# ProgrammateurFilPilote_1_1.net
KiCad netlist of a schematic drawn in EAGLE
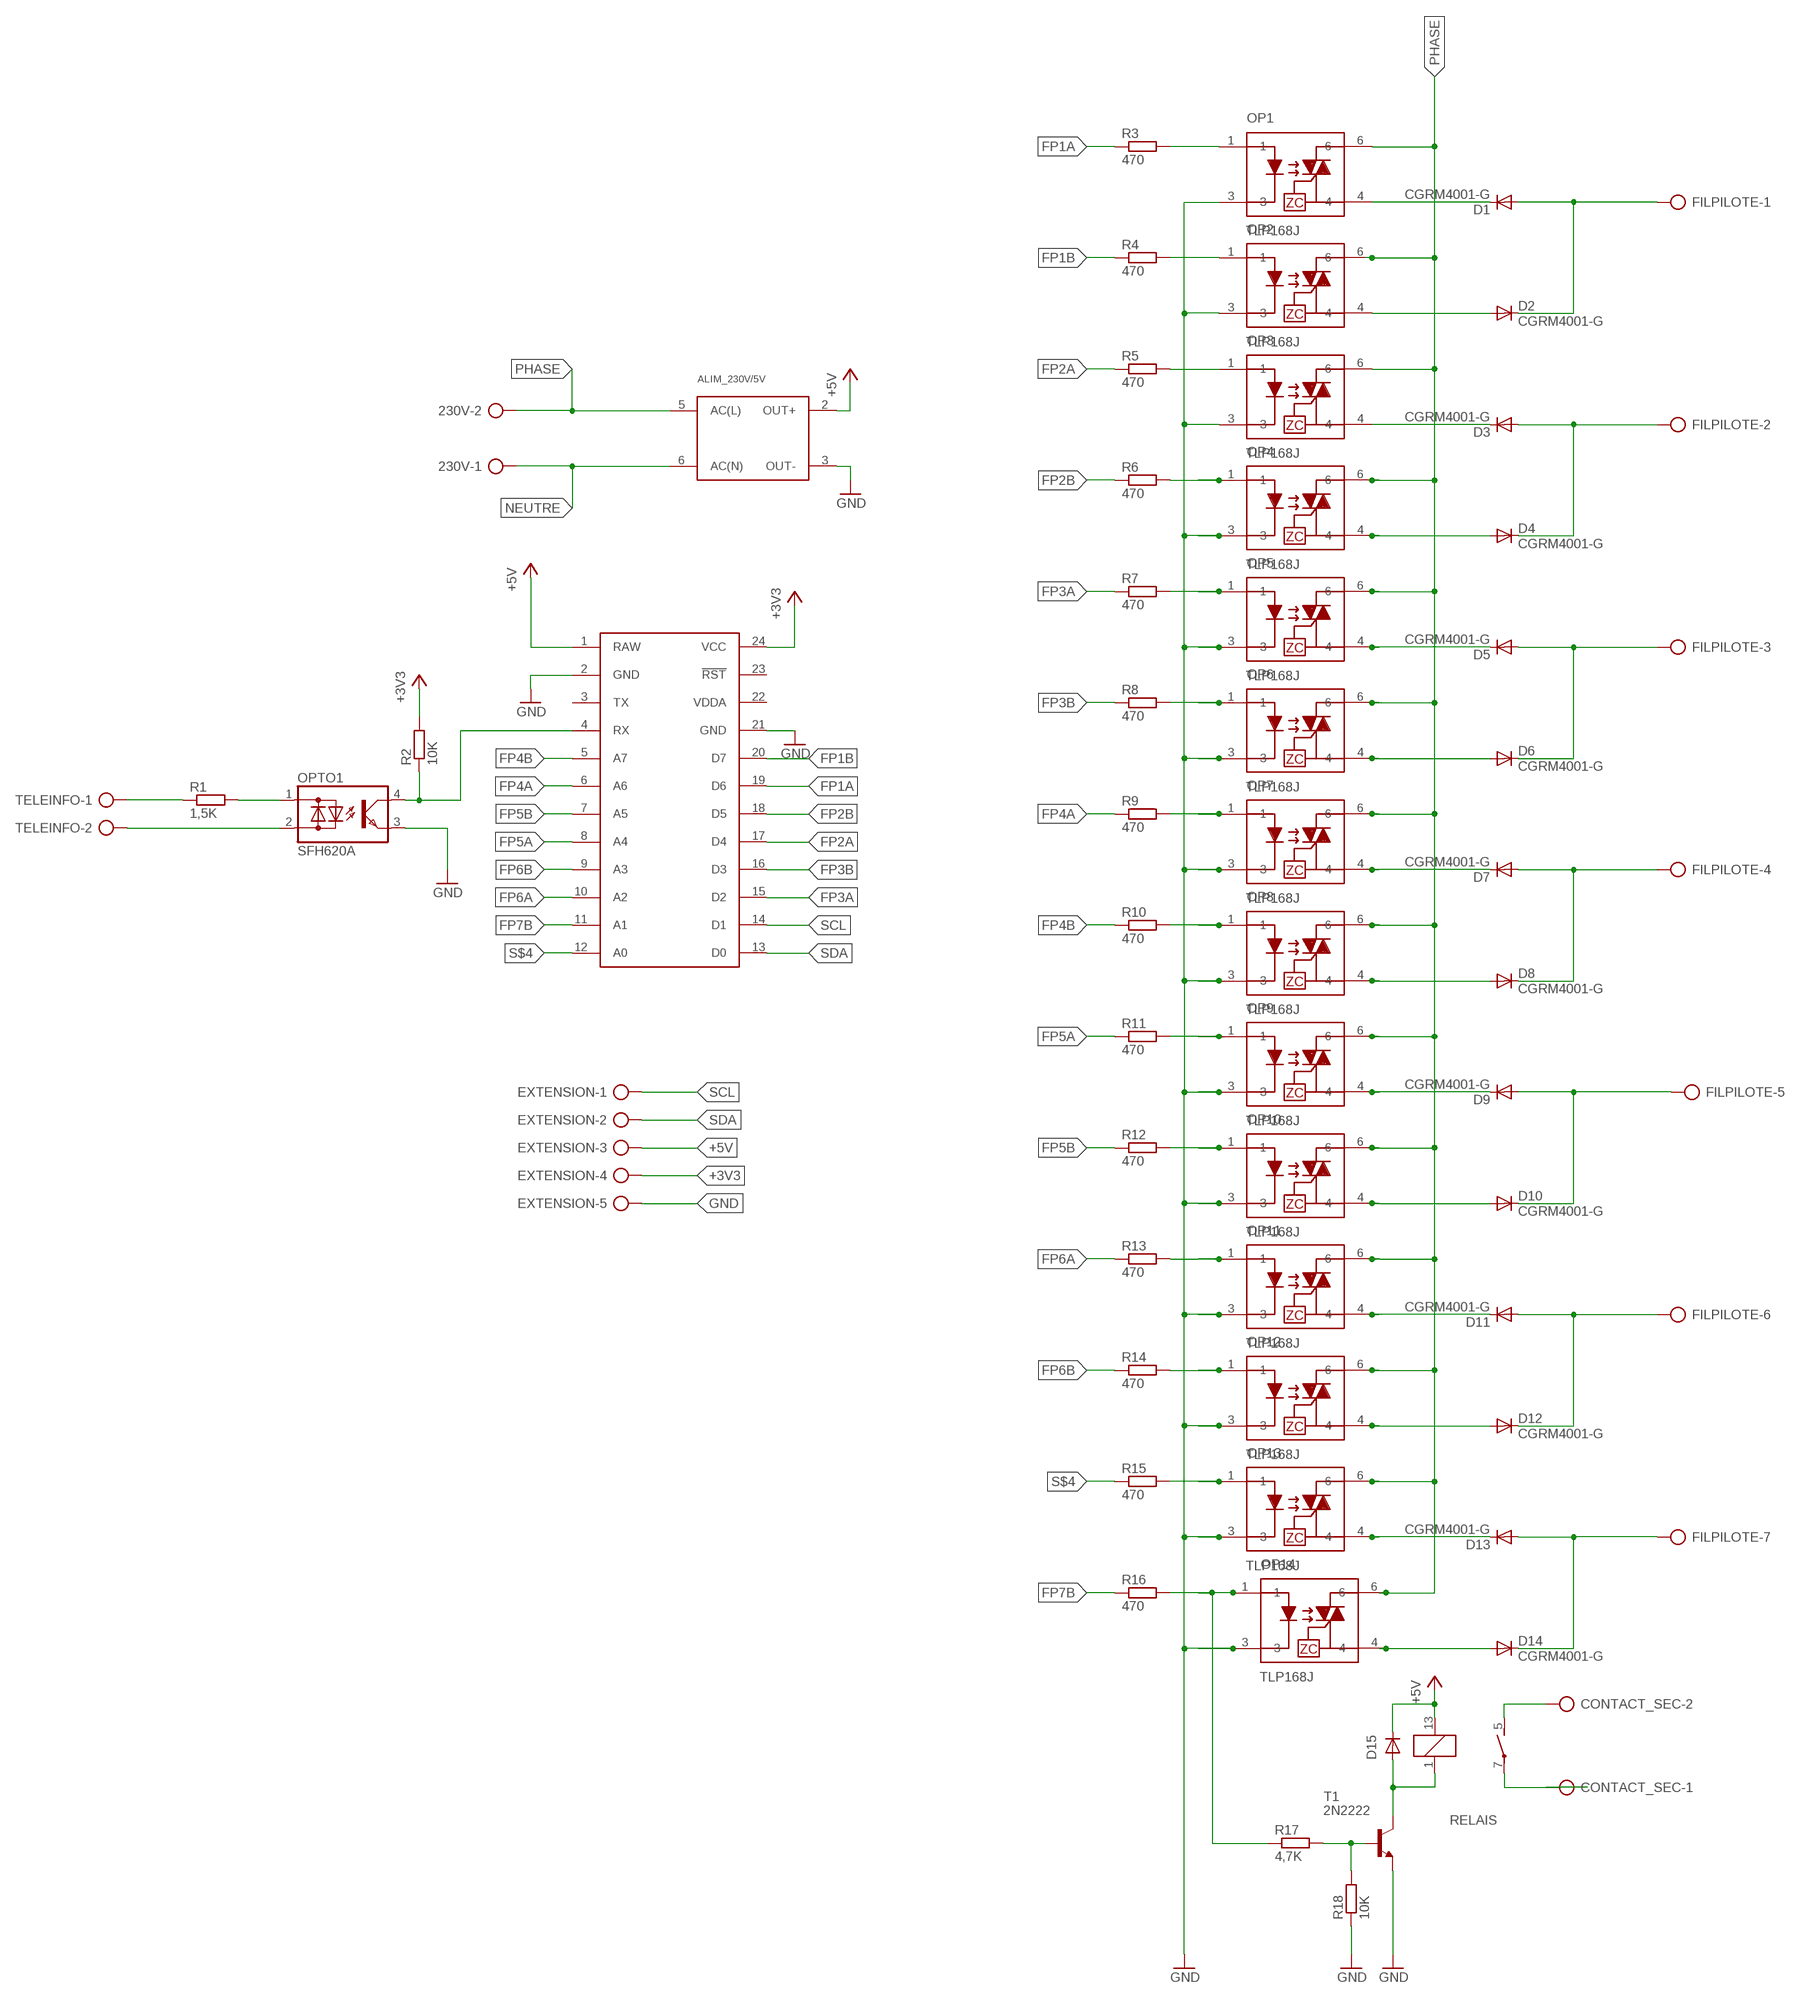
[diagram p0: schematic, sheet 1]

(export (version "E")
  (design (tool "Eeschema 10.0.6"))
  (components
    (comp (ref "230V")
      (value "AK500/2")
      (footprint "eagle-import:AK500_2")
      (libsource (lib "eagle-import") (part "AK500/2"))
    )
    (comp (ref "ALIM_230V/5V")
      (value "TMLM04-SINGLE")
      (footprint "eagle-import:TMLM04")
      (libsource (lib "eagle-import") (part "TMLM04-SINGLE"))
    )
    (comp (ref "CONTACT_SEC")
      (value "AK500/2")
      (footprint "eagle-import:AK500_2")
      (libsource (lib "eagle-import") (part "AK500/2"))
    )
    (comp (ref "D1")
      (value "CGRM4001-G")
      (footprint "eagle-import:SOD-123_MINI-SMA")
      (libsource (lib "eagle-import") (part "CGRM400-G1"))
    )
    (comp (ref "D2")
      (value "CGRM4001-G")
      (footprint "eagle-import:SOD-123_MINI-SMA")
      (libsource (lib "eagle-import") (part "CGRM400-G1"))
    )
    (comp (ref "D3")
      (value "CGRM4001-G")
      (footprint "eagle-import:SOD-123_MINI-SMA")
      (libsource (lib "eagle-import") (part "CGRM400-G1"))
    )
    (comp (ref "D4")
      (value "CGRM4001-G")
      (footprint "eagle-import:SOD-123_MINI-SMA")
      (libsource (lib "eagle-import") (part "CGRM400-G1"))
    )
    (comp (ref "D5")
      (value "CGRM4001-G")
      (footprint "eagle-import:SOD-123_MINI-SMA")
      (libsource (lib "eagle-import") (part "CGRM400-G1"))
    )
    (comp (ref "D6")
      (value "CGRM4001-G")
      (footprint "eagle-import:SOD-123_MINI-SMA")
      (libsource (lib "eagle-import") (part "CGRM400-G1"))
    )
    (comp (ref "D7")
      (value "CGRM4001-G")
      (footprint "eagle-import:SOD-123_MINI-SMA")
      (libsource (lib "eagle-import") (part "CGRM400-G1"))
    )
    (comp (ref "D8")
      (value "CGRM4001-G")
      (footprint "eagle-import:SOD-123_MINI-SMA")
      (libsource (lib "eagle-import") (part "CGRM400-G1"))
    )
    (comp (ref "D9")
      (value "CGRM4001-G")
      (footprint "eagle-import:SOD-123_MINI-SMA")
      (libsource (lib "eagle-import") (part "CGRM400-G1"))
    )
    (comp (ref "D10")
      (value "CGRM4001-G")
      (footprint "eagle-import:SOD-123_MINI-SMA")
      (libsource (lib "eagle-import") (part "CGRM400-G1"))
    )
    (comp (ref "D11")
      (value "CGRM4001-G")
      (footprint "eagle-import:SOD-123_MINI-SMA")
      (libsource (lib "eagle-import") (part "CGRM400-G1"))
    )
    (comp (ref "D12")
      (value "CGRM4001-G")
      (footprint "eagle-import:SOD-123_MINI-SMA")
      (libsource (lib "eagle-import") (part "CGRM400-G1"))
    )
    (comp (ref "D13")
      (value "CGRM4001-G")
      (footprint "eagle-import:SOD-123_MINI-SMA")
      (libsource (lib "eagle-import") (part "CGRM400-G1"))
    )
    (comp (ref "D14")
      (value "CGRM4001-G")
      (footprint "eagle-import:SOD-123_MINI-SMA")
      (libsource (lib "eagle-import") (part "CGRM400-G1"))
    )
    (comp (ref "D15")
      (value "CGRM4001-G")
      (footprint "eagle-import:SOD-123_MINI-SMA")
      (libsource (lib "eagle-import") (part "CGRM400-G1"))
    )
    (comp (ref "EXTENSION")
      (value "AK500/5")
      (footprint "eagle-import:AK500_5")
      (libsource (lib "eagle-import") (part "AK500/5"))
    )
    (comp (ref "FILPILOTE")
      (value "AK500/7")
      (footprint "eagle-import:AK500_7")
      (libsource (lib "eagle-import") (part "AK500/7"))
    )
    (comp (ref "OP1")
      (value "TLP168J")
      (footprint "eagle-import:MFSOP-4")
      (libsource (lib "eagle-import") (part "TLP168J"))
    )
    (comp (ref "OP2")
      (value "TLP168J")
      (footprint "eagle-import:MFSOP-4")
      (libsource (lib "eagle-import") (part "TLP168J"))
    )
    (comp (ref "OP3")
      (value "TLP168J")
      (footprint "eagle-import:MFSOP-4")
      (libsource (lib "eagle-import") (part "TLP168J"))
    )
    (comp (ref "OP4")
      (value "TLP168J")
      (footprint "eagle-import:MFSOP-4")
      (libsource (lib "eagle-import") (part "TLP168J"))
    )
    (comp (ref "OP5")
      (value "TLP168J")
      (footprint "eagle-import:MFSOP-4")
      (libsource (lib "eagle-import") (part "TLP168J"))
    )
    (comp (ref "OP6")
      (value "TLP168J")
      (footprint "eagle-import:MFSOP-4")
      (libsource (lib "eagle-import") (part "TLP168J"))
    )
    (comp (ref "OP7")
      (value "TLP168J")
      (footprint "eagle-import:MFSOP-4")
      (libsource (lib "eagle-import") (part "TLP168J"))
    )
    (comp (ref "OP8")
      (value "TLP168J")
      (footprint "eagle-import:MFSOP-4")
      (libsource (lib "eagle-import") (part "TLP168J"))
    )
    (comp (ref "OP9")
      (value "TLP168J")
      (footprint "eagle-import:MFSOP-4")
      (libsource (lib "eagle-import") (part "TLP168J"))
    )
    (comp (ref "OP10")
      (value "TLP168J")
      (footprint "eagle-import:MFSOP-4")
      (libsource (lib "eagle-import") (part "TLP168J"))
    )
    (comp (ref "OP11")
      (value "TLP168J")
      (footprint "eagle-import:MFSOP-4")
      (libsource (lib "eagle-import") (part "TLP168J"))
    )
    (comp (ref "OP12")
      (value "TLP168J")
      (footprint "eagle-import:MFSOP-4")
      (libsource (lib "eagle-import") (part "TLP168J"))
    )
    (comp (ref "OP13")
      (value "TLP168J")
      (footprint "eagle-import:MFSOP-4")
      (libsource (lib "eagle-import") (part "TLP168J"))
    )
    (comp (ref "OP14")
      (value "TLP168J")
      (footprint "eagle-import:MFSOP-4")
      (libsource (lib "eagle-import") (part "TLP168J"))
    )
    (comp (ref "OPTO1")
      (value "SFH620A")
      (footprint "eagle-import:DIL04")
      (fields (field (name "MPN") "SFH620A-2"))
      (libsource (lib "eagle-import") (part "SFH620A"))
    )
    (comp (ref "R1")
      (value "1,5K")
      (footprint "eagle-import:R1206")
      (libsource (lib "eagle-import") (part "R-EU_R1206"))
    )
    (comp (ref "R2")
      (value "10K")
      (footprint "eagle-import:R1206")
      (libsource (lib "eagle-import") (part "R-EU_R1206"))
    )
    (comp (ref "R3")
      (value "470")
      (footprint "eagle-import:R1206")
      (libsource (lib "eagle-import") (part "R-EU_R1206"))
    )
    (comp (ref "R4")
      (value "470")
      (footprint "eagle-import:R1206")
      (libsource (lib "eagle-import") (part "R-EU_R1206"))
    )
    (comp (ref "R5")
      (value "470")
      (footprint "eagle-import:R1206")
      (libsource (lib "eagle-import") (part "R-EU_R1206"))
    )
    (comp (ref "R6")
      (value "470")
      (footprint "eagle-import:R1206")
      (libsource (lib "eagle-import") (part "R-EU_R1206"))
    )
    (comp (ref "R7")
      (value "470")
      (footprint "eagle-import:R1206")
      (libsource (lib "eagle-import") (part "R-EU_R1206"))
    )
    (comp (ref "R8")
      (value "470")
      (footprint "eagle-import:R1206")
      (libsource (lib "eagle-import") (part "R-EU_R1206"))
    )
    (comp (ref "R9")
      (value "470")
      (footprint "eagle-import:R1206")
      (libsource (lib "eagle-import") (part "R-EU_R1206"))
    )
    (comp (ref "R10")
      (value "470")
      (footprint "eagle-import:R1206")
      (libsource (lib "eagle-import") (part "R-EU_R1206"))
    )
    (comp (ref "R11")
      (value "470")
      (footprint "eagle-import:R1206")
      (libsource (lib "eagle-import") (part "R-EU_R1206"))
    )
    (comp (ref "R12")
      (value "470")
      (footprint "eagle-import:R1206")
      (libsource (lib "eagle-import") (part "R-EU_R1206"))
    )
    (comp (ref "R13")
      (value "470")
      (footprint "eagle-import:R1206")
      (libsource (lib "eagle-import") (part "R-EU_R1206"))
    )
    (comp (ref "R14")
      (value "470")
      (footprint "eagle-import:R1206")
      (libsource (lib "eagle-import") (part "R-EU_R1206"))
    )
    (comp (ref "R15")
      (value "470")
      (footprint "eagle-import:R1206")
      (libsource (lib "eagle-import") (part "R-EU_R1206"))
    )
    (comp (ref "R16")
      (value "470")
      (footprint "eagle-import:R1206")
      (libsource (lib "eagle-import") (part "R-EU_R1206"))
    )
    (comp (ref "R17")
      (value "4,7K")
      (footprint "eagle-import:R1206")
      (libsource (lib "eagle-import") (part "R-EU_R1206"))
    )
    (comp (ref "R18")
      (value "10K")
      (footprint "eagle-import:R1206")
      (libsource (lib "eagle-import") (part "R-EU_R1206"))
    )
    (comp (ref "RELAIS")
      (value "Relais G6D")
      (footprint "eagle-import:G6D")
      (libsource (lib "eagle-import") (part "G6D?-1A-ASI12VDC"))
    )
    (comp (ref "SPARKCORE")
      (value "SPARK_CORECORE")
      (footprint "eagle-import:SPARK_CORE")
      (libsource (lib "eagle-import") (part "SPARK_CORECORE"))
    )
    (comp (ref "T1")
      (value "2N2222")
      (footprint "eagle-import:TO92-EBC")
      (libsource (lib "eagle-import") (part "-NPN-TO92-EBC2N2222"))
    )
    (comp (ref "TELEINFO")
      (value "AK500/2")
      (footprint "eagle-import:AK500_2")
      (libsource (lib "eagle-import") (part "AK500/2"))
    )
  )
  (nets
    (net (code "1") (name "+3V3") (class "Default")
      (node (ref "EXTENSION") (pin "4") (pinfunction "KL_4") (pintype "passive"))
      (node (ref "R2") (pin "2") (pinfunction "2_2") (pintype "passive"))
      (node (ref "SPARKCORE") (pin "24") (pinfunction "VCC_24") (pintype "power_in"))
    )
    (net (code "2") (name "+5V") (class "Default")
      (node (ref "ALIM_230V/5V") (pin "2") (pinfunction "OUT+_2") (pintype "passive"))
      (node (ref "D15") (pin "C") (pinfunction "C_C") (pintype "passive"))
      (node (ref "EXTENSION") (pin "3") (pinfunction "KL_3") (pintype "passive"))
      (node (ref "RELAIS") (pin "13") (pinfunction "2_13") (pintype "passive"))
      (node (ref "SPARKCORE") (pin "1") (pinfunction "RAW_1") (pintype "power_in"))
    )
    (net (code "3") (name "/VDDA") (class "Default")
      (node (ref "SPARKCORE") (pin "22") (pinfunction "VDDA_22") (pintype "power_in"))
    )
    (net (code "4") (name "FP1A") (class "Default")
      (node (ref "R3") (pin "1") (pinfunction "1_1") (pintype "passive"))
      (node (ref "SPARKCORE") (pin "19") (pinfunction "D6_19") (pintype "bidirectional"))
    )
    (net (code "5") (name "FP1B") (class "Default")
      (node (ref "R4") (pin "1") (pinfunction "1_1") (pintype "passive"))
      (node (ref "SPARKCORE") (pin "20") (pinfunction "D7_20") (pintype "bidirectional"))
    )
    (net (code "6") (name "FP2A") (class "Default")
      (node (ref "R5") (pin "1") (pinfunction "1_1") (pintype "passive"))
      (node (ref "SPARKCORE") (pin "17") (pinfunction "D4_17") (pintype "bidirectional"))
    )
    (net (code "7") (name "FP2B") (class "Default")
      (node (ref "R6") (pin "1") (pinfunction "1_1") (pintype "passive"))
      (node (ref "SPARKCORE") (pin "18") (pinfunction "D5_18") (pintype "bidirectional"))
    )
    (net (code "8") (name "FP3A") (class "Default")
      (node (ref "R7") (pin "1") (pinfunction "1_1") (pintype "passive"))
      (node (ref "SPARKCORE") (pin "15") (pinfunction "D2_15") (pintype "bidirectional"))
    )
    (net (code "9") (name "FP3B") (class "Default")
      (node (ref "R8") (pin "1") (pinfunction "1_1") (pintype "passive"))
      (node (ref "SPARKCORE") (pin "16") (pinfunction "D3_16") (pintype "bidirectional"))
    )
    (net (code "10") (name "FP4A") (class "Default")
      (node (ref "R9") (pin "1") (pinfunction "1_1") (pintype "passive"))
      (node (ref "SPARKCORE") (pin "6") (pinfunction "A6_6") (pintype "bidirectional"))
    )
    (net (code "11") (name "FP4B") (class "Default")
      (node (ref "R10") (pin "1") (pinfunction "1_1") (pintype "passive"))
      (node (ref "SPARKCORE") (pin "5") (pinfunction "A7_5") (pintype "bidirectional"))
    )
    (net (code "12") (name "FP5A") (class "Default")
      (node (ref "R11") (pin "1") (pinfunction "1_1") (pintype "passive"))
      (node (ref "SPARKCORE") (pin "8") (pinfunction "A4_8") (pintype "bidirectional"))
    )
    (net (code "13") (name "FP5B") (class "Default")
      (node (ref "R12") (pin "1") (pinfunction "1_1") (pintype "passive"))
      (node (ref "SPARKCORE") (pin "7") (pinfunction "A5_7") (pintype "bidirectional"))
    )
    (net (code "14") (name "FP6A") (class "Default")
      (node (ref "R13") (pin "1") (pinfunction "1_1") (pintype "passive"))
      (node (ref "SPARKCORE") (pin "10") (pinfunction "A2_10") (pintype "bidirectional"))
    )
    (net (code "15") (name "FP6B") (class "Default")
      (node (ref "R14") (pin "1") (pinfunction "1_1") (pintype "passive"))
      (node (ref "SPARKCORE") (pin "9") (pinfunction "A3_9") (pintype "bidirectional"))
    )
    (net (code "16") (name "FP7B") (class "Default")
      (node (ref "R16") (pin "1") (pinfunction "1_1") (pintype "passive"))
      (node (ref "SPARKCORE") (pin "11") (pinfunction "A1_11") (pintype "bidirectional"))
    )
    (net (code "17") (name "GND") (class "Default")
      (node (ref "ALIM_230V/5V") (pin "3") (pinfunction "OUT-_3") (pintype "passive"))
      (node (ref "EXTENSION") (pin "5") (pinfunction "KL_5") (pintype "passive"))
      (node (ref "OP1") (pin "3") (pinfunction "3_3") (pintype "bidirectional"))
      (node (ref "OP10") (pin "3") (pinfunction "3_3") (pintype "bidirectional"))
      (node (ref "OP11") (pin "3") (pinfunction "3_3") (pintype "bidirectional"))
      (node (ref "OP12") (pin "3") (pinfunction "3_3") (pintype "bidirectional"))
      (node (ref "OP13") (pin "3") (pinfunction "3_3") (pintype "bidirectional"))
      (node (ref "OP14") (pin "3") (pinfunction "3_3") (pintype "bidirectional"))
      (node (ref "OP2") (pin "3") (pinfunction "3_3") (pintype "bidirectional"))
      (node (ref "OP3") (pin "3") (pinfunction "3_3") (pintype "bidirectional"))
      (node (ref "OP4") (pin "3") (pinfunction "3_3") (pintype "bidirectional"))
      (node (ref "OP5") (pin "3") (pinfunction "3_3") (pintype "bidirectional"))
      (node (ref "OP6") (pin "3") (pinfunction "3_3") (pintype "bidirectional"))
      (node (ref "OP7") (pin "3") (pinfunction "3_3") (pintype "bidirectional"))
      (node (ref "OP8") (pin "3") (pinfunction "3_3") (pintype "bidirectional"))
      (node (ref "OP9") (pin "3") (pinfunction "3_3") (pintype "bidirectional"))
      (node (ref "OPTO1") (pin "3") (pinfunction "E_3") (pintype "passive"))
      (node (ref "R18") (pin "1") (pinfunction "1_1") (pintype "passive"))
      (node (ref "SPARKCORE") (pin "2") (pinfunction "GND_2") (pintype "power_in"))
      (node (ref "SPARKCORE") (pin "21") (pinfunction "GND_21") (pintype "power_in"))
      (node (ref "T1") (pin "E") (pinfunction "E_E") (pintype "passive"))
    )
    (net (code "18") (name "NEUTRE") (class "Default")
      (node (ref "230V") (pin "1") (pinfunction "KL_1") (pintype "passive"))
      (node (ref "ALIM_230V/5V") (pin "6") (pinfunction "AC(N)_6") (pintype "input"))
    )
    (net (code "19") (name "Net-(CONTACT_SECA-KL)") (class "Default")
      (node (ref "CONTACT_SEC") (pin "1") (pinfunction "KL_1") (pintype "passive"))
      (node (ref "RELAIS") (pin "7") (pinfunction "P_7") (pintype "passive"))
    )
    (net (code "20") (name "Net-(CONTACT_SECB-KL)") (class "Default")
      (node (ref "CONTACT_SEC") (pin "2") (pinfunction "KL_2") (pintype "passive"))
      (node (ref "RELAIS") (pin "5") (pinfunction "S_5") (pintype "passive"))
    )
    (net (code "21") (name "Net-(D1-PadC)") (class "Default")
      (node (ref "D1") (pin "C") (pinfunction "C_C") (pintype "passive"))
      (node (ref "OP1") (pin "4") (pinfunction "4_4") (pintype "bidirectional"))
    )
    (net (code "22") (name "Net-(D2-PadA)") (class "Default")
      (node (ref "D2") (pin "A") (pinfunction "A_A") (pintype "passive"))
      (node (ref "OP2") (pin "4") (pinfunction "4_4") (pintype "bidirectional"))
    )
    (net (code "23") (name "Net-(D3-PadC)") (class "Default")
      (node (ref "D3") (pin "C") (pinfunction "C_C") (pintype "passive"))
      (node (ref "OP3") (pin "4") (pinfunction "4_4") (pintype "bidirectional"))
    )
    (net (code "24") (name "Net-(D4-PadA)") (class "Default")
      (node (ref "D4") (pin "A") (pinfunction "A_A") (pintype "passive"))
      (node (ref "OP4") (pin "4") (pinfunction "4_4") (pintype "bidirectional"))
    )
    (net (code "25") (name "Net-(D5-PadC)") (class "Default")
      (node (ref "D5") (pin "C") (pinfunction "C_C") (pintype "passive"))
      (node (ref "OP5") (pin "4") (pinfunction "4_4") (pintype "bidirectional"))
    )
    (net (code "26") (name "Net-(D6-PadA)") (class "Default")
      (node (ref "D6") (pin "A") (pinfunction "A_A") (pintype "passive"))
      (node (ref "OP6") (pin "4") (pinfunction "4_4") (pintype "bidirectional"))
    )
    (net (code "27") (name "Net-(D7-PadC)") (class "Default")
      (node (ref "D7") (pin "C") (pinfunction "C_C") (pintype "passive"))
      (node (ref "OP7") (pin "4") (pinfunction "4_4") (pintype "bidirectional"))
    )
    (net (code "28") (name "Net-(D8-PadA)") (class "Default")
      (node (ref "D8") (pin "A") (pinfunction "A_A") (pintype "passive"))
      (node (ref "OP8") (pin "4") (pinfunction "4_4") (pintype "bidirectional"))
    )
    (net (code "29") (name "Net-(D9-PadC)") (class "Default")
      (node (ref "D9") (pin "C") (pinfunction "C_C") (pintype "passive"))
      (node (ref "OP9") (pin "4") (pinfunction "4_4") (pintype "bidirectional"))
    )
    (net (code "30") (name "Net-(D10-PadA)") (class "Default")
      (node (ref "D10") (pin "A") (pinfunction "A_A") (pintype "passive"))
      (node (ref "OP10") (pin "4") (pinfunction "4_4") (pintype "bidirectional"))
    )
    (net (code "31") (name "Net-(D11-PadC)") (class "Default")
      (node (ref "D11") (pin "C") (pinfunction "C_C") (pintype "passive"))
      (node (ref "OP11") (pin "4") (pinfunction "4_4") (pintype "bidirectional"))
    )
    (net (code "32") (name "Net-(D12-PadA)") (class "Default")
      (node (ref "D12") (pin "A") (pinfunction "A_A") (pintype "passive"))
      (node (ref "OP12") (pin "4") (pinfunction "4_4") (pintype "bidirectional"))
    )
    (net (code "33") (name "Net-(D13-PadC)") (class "Default")
      (node (ref "D13") (pin "C") (pinfunction "C_C") (pintype "passive"))
      (node (ref "OP13") (pin "4") (pinfunction "4_4") (pintype "bidirectional"))
    )
    (net (code "34") (name "Net-(D14-PadA)") (class "Default")
      (node (ref "D14") (pin "A") (pinfunction "A_A") (pintype "passive"))
      (node (ref "OP14") (pin "4") (pinfunction "4_4") (pintype "bidirectional"))
    )
    (net (code "35") (name "Net-(D15-PadA)") (class "Default")
      (node (ref "D15") (pin "A") (pinfunction "A_A") (pintype "passive"))
      (node (ref "RELAIS") (pin "1") (pinfunction "1_1") (pintype "passive"))
      (node (ref "T1") (pin "C") (pinfunction "C_C") (pintype "passive"))
    )
    (net (code "36") (name "Net-(FILPILOTEA-KL)") (class "Default")
      (node (ref "D1") (pin "A") (pinfunction "A_A") (pintype "passive"))
      (node (ref "D2") (pin "C") (pinfunction "C_C") (pintype "passive"))
      (node (ref "FILPILOTE") (pin "1") (pinfunction "KL_1") (pintype "passive"))
    )
    (net (code "37") (name "Net-(FILPILOTEB-KL)") (class "Default")
      (node (ref "D3") (pin "A") (pinfunction "A_A") (pintype "passive"))
      (node (ref "D4") (pin "C") (pinfunction "C_C") (pintype "passive"))
      (node (ref "FILPILOTE") (pin "2") (pinfunction "KL_2") (pintype "passive"))
    )
    (net (code "38") (name "Net-(FILPILOTEC-KL)") (class "Default")
      (node (ref "D5") (pin "A") (pinfunction "A_A") (pintype "passive"))
      (node (ref "D6") (pin "C") (pinfunction "C_C") (pintype "passive"))
      (node (ref "FILPILOTE") (pin "3") (pinfunction "KL_3") (pintype "passive"))
    )
    (net (code "39") (name "Net-(FILPILOTED-KL)") (class "Default")
      (node (ref "D7") (pin "A") (pinfunction "A_A") (pintype "passive"))
      (node (ref "D8") (pin "C") (pinfunction "C_C") (pintype "passive"))
      (node (ref "FILPILOTE") (pin "4") (pinfunction "KL_4") (pintype "passive"))
    )
    (net (code "40") (name "Net-(FILPILOTEE-KL)") (class "Default")
      (node (ref "D10") (pin "C") (pinfunction "C_C") (pintype "passive"))
      (node (ref "D9") (pin "A") (pinfunction "A_A") (pintype "passive"))
      (node (ref "FILPILOTE") (pin "5") (pinfunction "KL_5") (pintype "passive"))
    )
    (net (code "41") (name "Net-(FILPILOTEF-KL)") (class "Default")
      (node (ref "D11") (pin "A") (pinfunction "A_A") (pintype "passive"))
      (node (ref "D12") (pin "C") (pinfunction "C_C") (pintype "passive"))
      (node (ref "FILPILOTE") (pin "6") (pinfunction "KL_6") (pintype "passive"))
    )
    (net (code "42") (name "Net-(FILPILOTEG-KL)") (class "Default")
      (node (ref "D13") (pin "A") (pinfunction "A_A") (pintype "passive"))
      (node (ref "D14") (pin "C") (pinfunction "C_C") (pintype "passive"))
      (node (ref "FILPILOTE") (pin "7") (pinfunction "KL_7") (pintype "passive"))
    )
    (net (code "43") (name "Net-(OP1-Pad1)") (class "Default")
      (node (ref "OP1") (pin "1") (pinfunction "1_1") (pintype "bidirectional"))
      (node (ref "R3") (pin "2") (pinfunction "2_2") (pintype "passive"))
    )
    (net (code "44") (name "Net-(OP2-Pad1)") (class "Default")
      (node (ref "OP2") (pin "1") (pinfunction "1_1") (pintype "bidirectional"))
      (node (ref "R4") (pin "2") (pinfunction "2_2") (pintype "passive"))
    )
    (net (code "45") (name "Net-(OP3-Pad1)") (class "Default")
      (node (ref "OP3") (pin "1") (pinfunction "1_1") (pintype "bidirectional"))
      (node (ref "R5") (pin "2") (pinfunction "2_2") (pintype "passive"))
    )
    (net (code "46") (name "Net-(OP4-Pad1)") (class "Default")
      (node (ref "OP4") (pin "1") (pinfunction "1_1") (pintype "bidirectional"))
      (node (ref "R6") (pin "2") (pinfunction "2_2") (pintype "passive"))
    )
    (net (code "47") (name "Net-(OP5-Pad1)") (class "Default")
      (node (ref "OP5") (pin "1") (pinfunction "1_1") (pintype "bidirectional"))
      (node (ref "R7") (pin "2") (pinfunction "2_2") (pintype "passive"))
    )
    (net (code "48") (name "Net-(OP6-Pad1)") (class "Default")
      (node (ref "OP6") (pin "1") (pinfunction "1_1") (pintype "bidirectional"))
      (node (ref "R8") (pin "2") (pinfunction "2_2") (pintype "passive"))
    )
    (net (code "49") (name "Net-(OP7-Pad1)") (class "Default")
      (node (ref "OP7") (pin "1") (pinfunction "1_1") (pintype "bidirectional"))
      (node (ref "R9") (pin "2") (pinfunction "2_2") (pintype "passive"))
    )
    (net (code "50") (name "Net-(OP8-Pad1)") (class "Default")
      (node (ref "OP8") (pin "1") (pinfunction "1_1") (pintype "bidirectional"))
      (node (ref "R10") (pin "2") (pinfunction "2_2") (pintype "passive"))
    )
    (net (code "51") (name "Net-(OP9-Pad1)") (class "Default")
      (node (ref "OP9") (pin "1") (pinfunction "1_1") (pintype "bidirectional"))
      (node (ref "R11") (pin "2") (pinfunction "2_2") (pintype "passive"))
    )
    (net (code "52") (name "Net-(OP10-Pad1)") (class "Default")
      (node (ref "OP10") (pin "1") (pinfunction "1_1") (pintype "bidirectional"))
      (node (ref "R12") (pin "2") (pinfunction "2_2") (pintype "passive"))
    )
    (net (code "53") (name "Net-(OP11-Pad1)") (class "Default")
      (node (ref "OP11") (pin "1") (pinfunction "1_1") (pintype "bidirectional"))
      (node (ref "R13") (pin "2") (pinfunction "2_2") (pintype "passive"))
    )
    (net (code "54") (name "Net-(OP12-Pad1)") (class "Default")
      (node (ref "OP12") (pin "1") (pinfunction "1_1") (pintype "bidirectional"))
      (node (ref "R14") (pin "2") (pinfunction "2_2") (pintype "passive"))
    )
    (net (code "55") (name "Net-(OP13-Pad1)") (class "Default")
      (node (ref "OP13") (pin "1") (pinfunction "1_1") (pintype "bidirectional"))
      (node (ref "R15") (pin "2") (pinfunction "2_2") (pintype "passive"))
    )
    (net (code "56") (name "Net-(OP14-Pad1)") (class "Default")
      (node (ref "OP14") (pin "1") (pinfunction "1_1") (pintype "bidirectional"))
      (node (ref "R16") (pin "2") (pinfunction "2_2") (pintype "passive"))
      (node (ref "R17") (pin "1") (pinfunction "1_1") (pintype "passive"))
    )
    (net (code "57") (name "Net-(OPTO1-AC1)") (class "Default")
      (node (ref "OPTO1") (pin "1") (pinfunction "AC1_1") (pintype "passive"))
      (node (ref "R1") (pin "2") (pinfunction "2_2") (pintype "passive"))
    )
    (net (code "58") (name "Net-(OPTO1-AC2)") (class "Default")
      (node (ref "OPTO1") (pin "2") (pinfunction "AC2_2") (pintype "passive"))
      (node (ref "TELEINFO") (pin "2") (pinfunction "KL_2") (pintype "passive"))
    )
    (net (code "59") (name "Net-(OPTO1-C)") (class "Default")
      (node (ref "OPTO1") (pin "4") (pinfunction "C_4") (pintype "passive"))
      (node (ref "R2") (pin "1") (pinfunction "1_1") (pintype "passive"))
      (node (ref "SPARKCORE") (pin "4") (pinfunction "RX_4") (pintype "bidirectional"))
    )
    (net (code "60") (name "Net-(R17-Pad2)") (class "Default")
      (node (ref "R17") (pin "2") (pinfunction "2_2") (pintype "passive"))
      (node (ref "R18") (pin "2") (pinfunction "2_2") (pintype "passive"))
      (node (ref "T1") (pin "B") (pinfunction "B_B") (pintype "passive"))
    )
    (net (code "61") (name "Net-(TELEINFOA-KL)") (class "Default")
      (node (ref "R1") (pin "1") (pinfunction "1_1") (pintype "passive"))
      (node (ref "TELEINFO") (pin "1") (pinfunction "KL_1") (pintype "passive"))
    )
    (net (code "62") (name "PHASE") (class "Default")
      (node (ref "230V") (pin "2") (pinfunction "KL_2") (pintype "passive"))
      (node (ref "ALIM_230V/5V") (pin "5") (pinfunction "AC(L)_5") (pintype "input"))
      (node (ref "OP1") (pin "6") (pinfunction "6_6") (pintype "bidirectional"))
      (node (ref "OP10") (pin "6") (pinfunction "6_6") (pintype "bidirectional"))
      (node (ref "OP11") (pin "6") (pinfunction "6_6") (pintype "bidirectional"))
      (node (ref "OP12") (pin "6") (pinfunction "6_6") (pintype "bidirectional"))
      (node (ref "OP13") (pin "6") (pinfunction "6_6") (pintype "bidirectional"))
      (node (ref "OP14") (pin "6") (pinfunction "6_6") (pintype "bidirectional"))
      (node (ref "OP2") (pin "6") (pinfunction "6_6") (pintype "bidirectional"))
      (node (ref "OP3") (pin "6") (pinfunction "6_6") (pintype "bidirectional"))
      (node (ref "OP4") (pin "6") (pinfunction "6_6") (pintype "bidirectional"))
      (node (ref "OP5") (pin "6") (pinfunction "6_6") (pintype "bidirectional"))
      (node (ref "OP6") (pin "6") (pinfunction "6_6") (pintype "bidirectional"))
      (node (ref "OP7") (pin "6") (pinfunction "6_6") (pintype "bidirectional"))
      (node (ref "OP8") (pin "6") (pinfunction "6_6") (pintype "bidirectional"))
      (node (ref "OP9") (pin "6") (pinfunction "6_6") (pintype "bidirectional"))
    )
    (net (code "63") (name "S$4") (class "Default")
      (node (ref "R15") (pin "1") (pinfunction "1_1") (pintype "passive"))
      (node (ref "SPARKCORE") (pin "12") (pinfunction "A0_12") (pintype "bidirectional"))
    )
    (net (code "64") (name "SCL") (class "Default")
      (node (ref "EXTENSION") (pin "1") (pinfunction "KL_1") (pintype "passive"))
      (node (ref "SPARKCORE") (pin "14") (pinfunction "D1_14") (pintype "bidirectional"))
    )
    (net (code "65") (name "SDA") (class "Default")
      (node (ref "EXTENSION") (pin "2") (pinfunction "KL_2") (pintype "passive"))
      (node (ref "SPARKCORE") (pin "13") (pinfunction "D0_13") (pintype "bidirectional"))
    )
    (net (code "66") (name "unconnected-(SPARKCORE-TX-Pad3)") (class "Default")
      (node (ref "SPARKCORE") (pin "3") (pinfunction "TX_3") (pintype "bidirectional"))
    )
    (net (code "67") (name "unconnected-(SPARKCORE-~{RST}-Pad23)") (class "Default")
      (node (ref "SPARKCORE") (pin "23") (pinfunction "~{RST}_23") (pintype "bidirectional"))
    )
  )
)
